# core_mcu.net
KiCad netlist of a schematic drawn in EAGLE
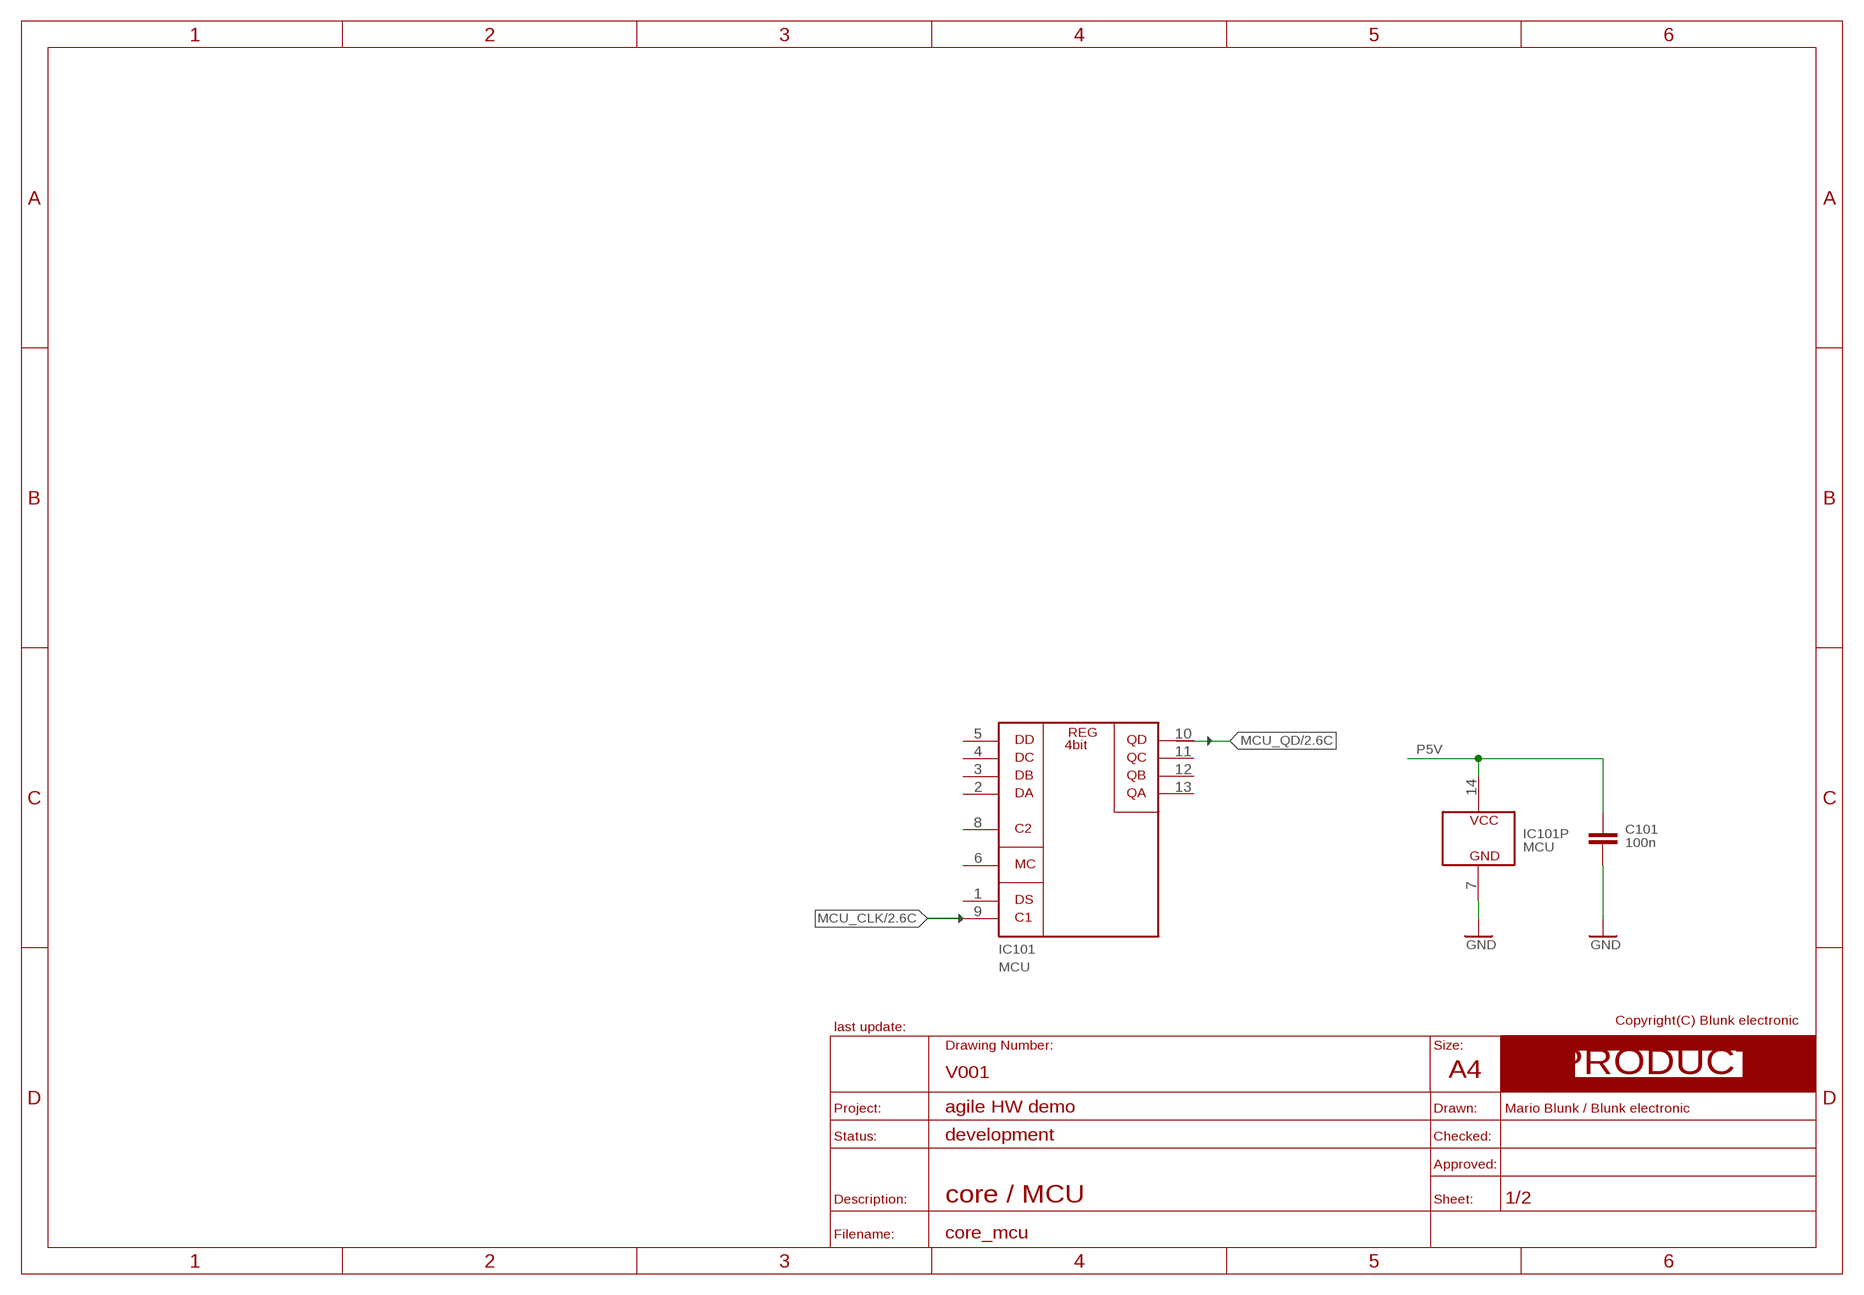
[diagram p0: schematic, sheet 1]
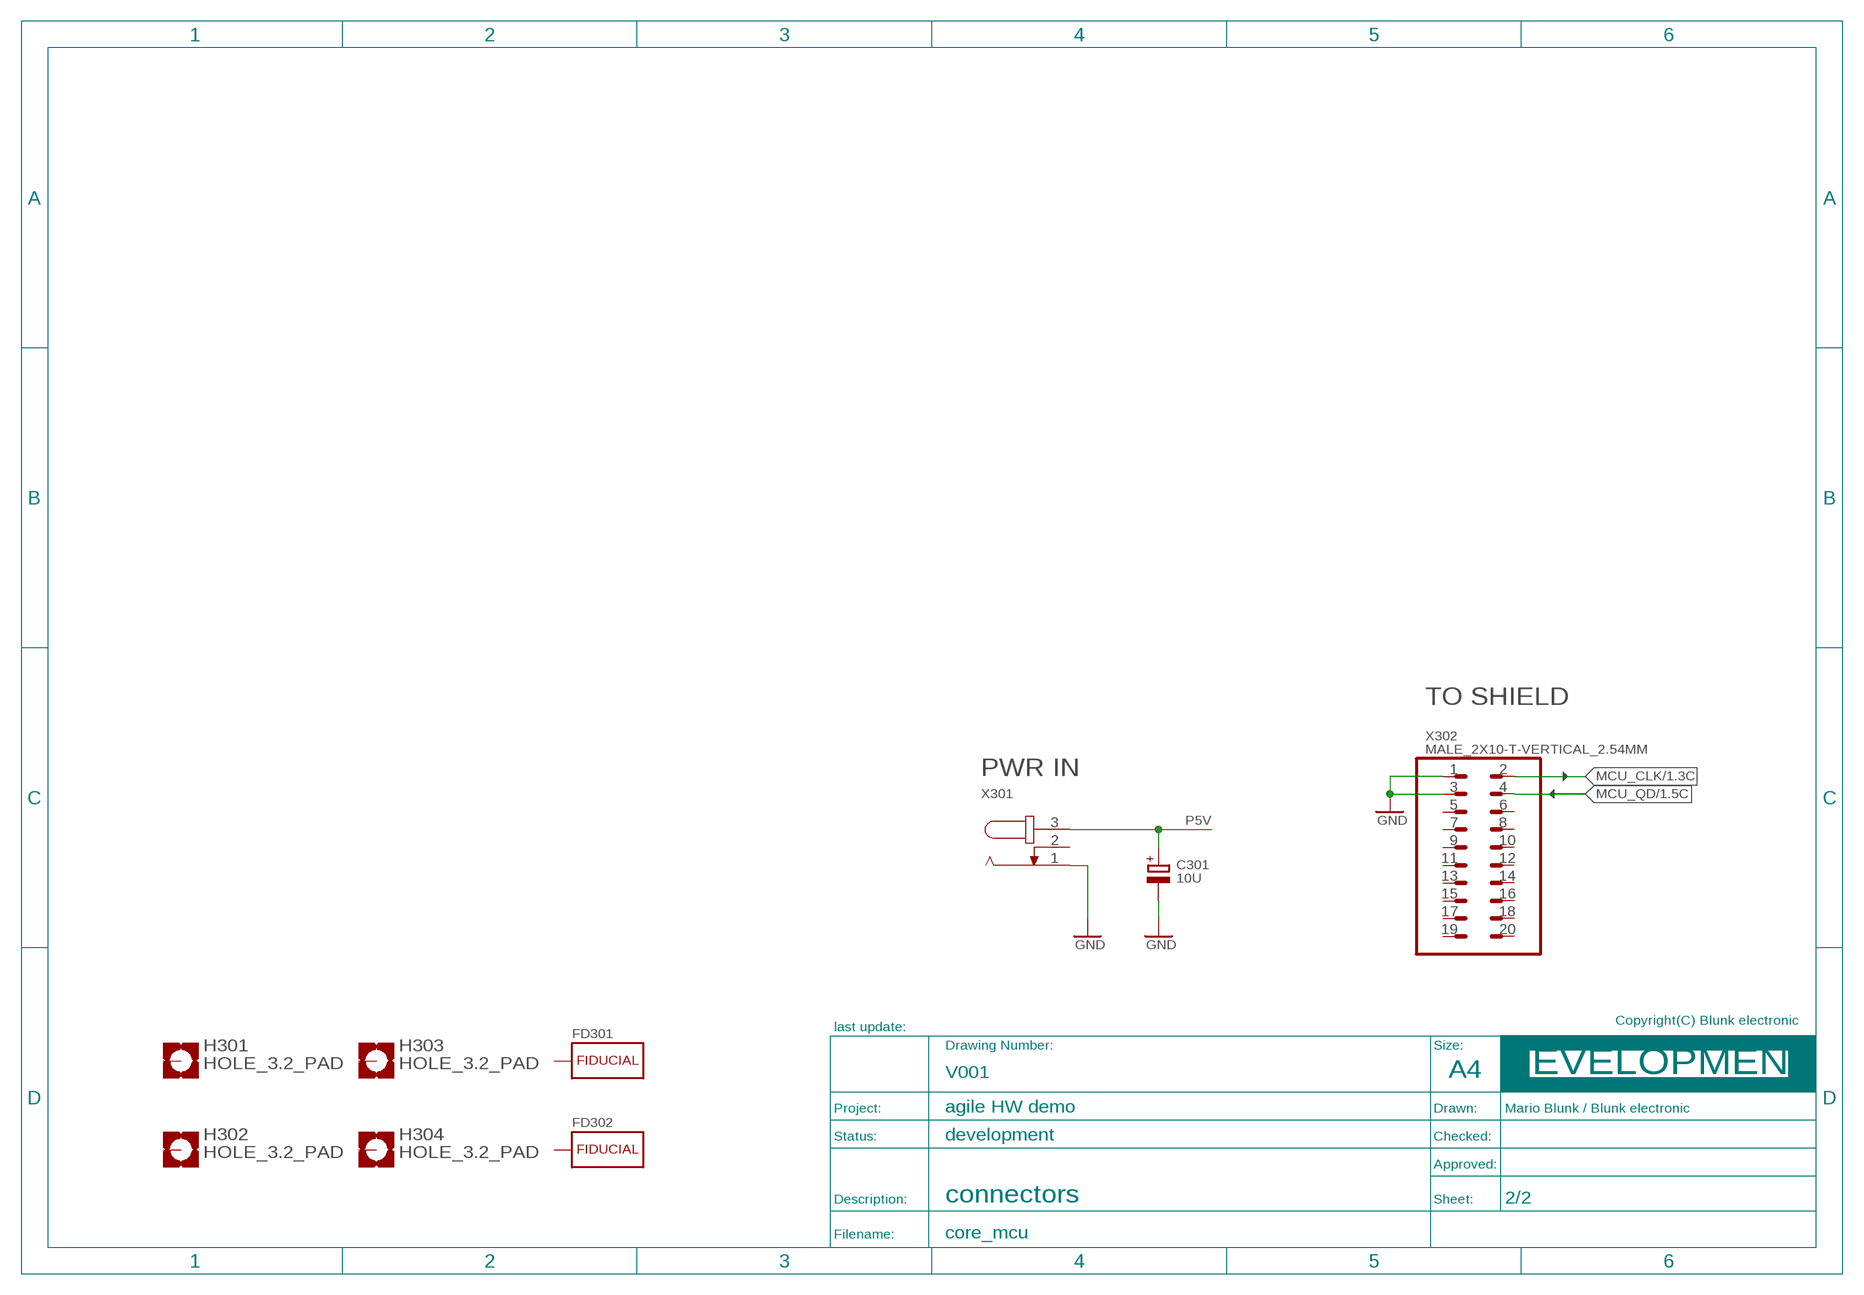
[diagram p1: schematic, sheet 2]

(export (version "E")
  (design (tool "Eeschema 10.0.6"))
  (components
    (comp (ref "C101")
      (value "100n")
      (footprint "eagle-import:S_0805")
      (libsource (lib "eagle-import") (part "C_S_0805"))
    )
    (comp (ref "IC101")
      (value "MCU")
      (footprint "eagle-import:T_NDIP14")
      (libsource (lib "eagle-import") (part "7495N"))
    )
    (comp (ref "C301")
      (value "10U")
      (footprint "eagle-import:S_6032")
      (libsource (lib "eagle-import") (part "C_POL_S_6032"))
    )
    (comp (ref "FD301")
      (value "FIDUCIAL_CROSSHAIR")
      (footprint "eagle-import:CROSSHAIR")
      (libsource (lib "eagle-import") (part "FIDUCIAL_CROSSHAIR"))
    )
    (comp (ref "FD302")
      (value "FIDUCIAL_CROSSHAIR")
      (footprint "eagle-import:CROSSHAIR")
      (libsource (lib "eagle-import") (part "FIDUCIAL_CROSSHAIR"))
    )
    (comp (ref "H301")
      (value "HOLE_3.2_PAD")
      (footprint "eagle-import:3.2_PAD")
      (libsource (lib "eagle-import") (part "HOLE_3.2_PAD"))
    )
    (comp (ref "H302")
      (value "HOLE_3.2_PAD")
      (footprint "eagle-import:3.2_PAD")
      (libsource (lib "eagle-import") (part "HOLE_3.2_PAD"))
    )
    (comp (ref "H303")
      (value "HOLE_3.2_PAD")
      (footprint "eagle-import:3.2_PAD")
      (libsource (lib "eagle-import") (part "HOLE_3.2_PAD"))
    )
    (comp (ref "H304")
      (value "HOLE_3.2_PAD")
      (footprint "eagle-import:3.2_PAD")
      (libsource (lib "eagle-import") (part "HOLE_3.2_PAD"))
    )
    (comp (ref "X301")
      (value "POWER_JACK-T-0")
      (footprint "eagle-import:T_POWER_JACK_SPC4077")
      (fields (field (name "FUNCTION") "PWR IN"))
      (libsource (lib "eagle-import") (part "POWER_JACK-T-0"))
    )
    (comp (ref "X302")
      (value "MALE_2X10-T-VERTICAL_2.54MM")
      (footprint "eagle-import:T_MALE_2X10_VERTICAL_GRID_2.54MM")
      (fields (field (name "FUNCTION") "TO SHIELD"))
      (libsource (lib "eagle-import") (part "MALE_2X10-T-VERTICAL_2.54MM"))
    )
  )
  (nets
    (net (code "1") (name "GND") (class "Default")
      (node (ref "C101") (pin "2") (pinfunction "2_2") (pintype "passive"))
      (node (ref "C301") (pin "-") (pinfunction "-_-") (pintype "passive"))
      (node (ref "IC101") (pin "7") (pinfunction "GND_7") (pintype "power_in"))
      (node (ref "X301") (pin "1") (pinfunction "1_1") (pintype "passive"))
      (node (ref "X302") (pin "1") (pinfunction "1_1") (pintype "passive"))
      (node (ref "X302") (pin "3") (pinfunction "3_3") (pintype "passive"))
    )
    (net (code "2") (name "MCU_CLK") (class "Default")
      (node (ref "IC101") (pin "9") (pinfunction "C1_9") (pintype "input"))
      (node (ref "X302") (pin "2") (pinfunction "2_2") (pintype "passive"))
    )
    (net (code "3") (name "MCU_QD") (class "Default")
      (node (ref "IC101") (pin "10") (pinfunction "QD_10") (pintype "output"))
      (node (ref "X302") (pin "4") (pinfunction "4_4") (pintype "passive"))
    )
    (net (code "4") (name "P5V") (class "Default")
      (node (ref "C101") (pin "1") (pinfunction "1_1") (pintype "passive"))
      (node (ref "C301") (pin "+") (pinfunction "+_+") (pintype "passive"))
      (node (ref "IC101") (pin "14") (pinfunction "VCC_14") (pintype "power_in"))
      (node (ref "X301") (pin "3") (pinfunction "3_3") (pintype "passive"))
    )
    (net (code "5") (name "unconnected-(FD301-NC-Pad1)") (class "Default")
      (node (ref "FD301") (pin "1") (pinfunction "NC_1") (pintype "no_connect"))
    )
    (net (code "6") (name "unconnected-(FD302-NC-Pad1)") (class "Default")
      (node (ref "FD302") (pin "1") (pinfunction "NC_1") (pintype "no_connect"))
    )
    (net (code "7") (name "unconnected-(H301-MOUNT-PadH1)") (class "Default")
      (node (ref "H301") (pin "H1") (pinfunction "MOUNT_H1") (pintype "passive"))
    )
    (net (code "8") (name "unconnected-(H302-MOUNT-PadH1)") (class "Default")
      (node (ref "H302") (pin "H1") (pinfunction "MOUNT_H1") (pintype "passive"))
    )
    (net (code "9") (name "unconnected-(H303-MOUNT-PadH1)") (class "Default")
      (node (ref "H303") (pin "H1") (pinfunction "MOUNT_H1") (pintype "passive"))
    )
    (net (code "10") (name "unconnected-(H304-MOUNT-PadH1)") (class "Default")
      (node (ref "H304") (pin "H1") (pinfunction "MOUNT_H1") (pintype "passive"))
    )
    (net (code "11") (name "unconnected-(IC101A-C2-Pad8)") (class "Default")
      (node (ref "IC101") (pin "8") (pinfunction "C2_8") (pintype "input"))
    )
    (net (code "12") (name "unconnected-(IC101A-DA-Pad2)") (class "Default")
      (node (ref "IC101") (pin "2") (pinfunction "DA_2") (pintype "input"))
    )
    (net (code "13") (name "unconnected-(IC101A-DB-Pad3)") (class "Default")
      (node (ref "IC101") (pin "3") (pinfunction "DB_3") (pintype "input"))
    )
    (net (code "14") (name "unconnected-(IC101A-DC-Pad4)") (class "Default")
      (node (ref "IC101") (pin "4") (pinfunction "DC_4") (pintype "input"))
    )
    (net (code "15") (name "unconnected-(IC101A-DD-Pad5)") (class "Default")
      (node (ref "IC101") (pin "5") (pinfunction "DD_5") (pintype "input"))
    )
    (net (code "16") (name "unconnected-(IC101A-DS-Pad1)") (class "Default")
      (node (ref "IC101") (pin "1") (pinfunction "DS_1") (pintype "input"))
    )
    (net (code "17") (name "unconnected-(IC101A-MC-Pad6)") (class "Default")
      (node (ref "IC101") (pin "6") (pinfunction "MC_6") (pintype "input"))
    )
    (net (code "18") (name "unconnected-(IC101A-QA-Pad13)") (class "Default")
      (node (ref "IC101") (pin "13") (pinfunction "QA_13") (pintype "output"))
    )
    (net (code "19") (name "unconnected-(IC101A-QB-Pad12)") (class "Default")
      (node (ref "IC101") (pin "12") (pinfunction "QB_12") (pintype "output"))
    )
    (net (code "20") (name "unconnected-(IC101A-QC-Pad11)") (class "Default")
      (node (ref "IC101") (pin "11") (pinfunction "QC_11") (pintype "output"))
    )
    (net (code "21") (name "unconnected-(X301-Pad2)") (class "Default")
      (node (ref "X301") (pin "2") (pinfunction "2_2") (pintype "passive"))
    )
    (net (code "22") (name "unconnected-(X302-Pad5)") (class "Default")
      (node (ref "X302") (pin "5") (pinfunction "5_5") (pintype "passive"))
    )
    (net (code "23") (name "unconnected-(X302-Pad6)") (class "Default")
      (node (ref "X302") (pin "6") (pinfunction "6_6") (pintype "passive"))
    )
    (net (code "24") (name "unconnected-(X302-Pad7)") (class "Default")
      (node (ref "X302") (pin "7") (pinfunction "7_7") (pintype "passive"))
    )
    (net (code "25") (name "unconnected-(X302-Pad8)") (class "Default")
      (node (ref "X302") (pin "8") (pinfunction "8_8") (pintype "passive"))
    )
    (net (code "26") (name "unconnected-(X302-Pad9)") (class "Default")
      (node (ref "X302") (pin "9") (pinfunction "9_9") (pintype "passive"))
    )
    (net (code "27") (name "unconnected-(X302-Pad10)") (class "Default")
      (node (ref "X302") (pin "10") (pinfunction "10_10") (pintype "passive"))
    )
    (net (code "28") (name "unconnected-(X302-Pad11)") (class "Default")
      (node (ref "X302") (pin "11") (pinfunction "11_11") (pintype "passive"))
    )
    (net (code "29") (name "unconnected-(X302-Pad12)") (class "Default")
      (node (ref "X302") (pin "12") (pinfunction "12_12") (pintype "passive"))
    )
    (net (code "30") (name "unconnected-(X302-Pad13)") (class "Default")
      (node (ref "X302") (pin "13") (pinfunction "13_13") (pintype "passive"))
    )
    (net (code "31") (name "unconnected-(X302-Pad14)") (class "Default")
      (node (ref "X302") (pin "14") (pinfunction "14_14") (pintype "passive"))
    )
    (net (code "32") (name "unconnected-(X302-Pad15)") (class "Default")
      (node (ref "X302") (pin "15") (pinfunction "15_15") (pintype "passive"))
    )
    (net (code "33") (name "unconnected-(X302-Pad16)") (class "Default")
      (node (ref "X302") (pin "16") (pinfunction "16_16") (pintype "passive"))
    )
    (net (code "34") (name "unconnected-(X302-Pad17)") (class "Default")
      (node (ref "X302") (pin "17") (pinfunction "17_17") (pintype "passive"))
    )
    (net (code "35") (name "unconnected-(X302-Pad18)") (class "Default")
      (node (ref "X302") (pin "18") (pinfunction "18_18") (pintype "passive"))
    )
    (net (code "36") (name "unconnected-(X302-Pad19)") (class "Default")
      (node (ref "X302") (pin "19") (pinfunction "19_19") (pintype "passive"))
    )
    (net (code "37") (name "unconnected-(X302-Pad20)") (class "Default")
      (node (ref "X302") (pin "20") (pinfunction "20_20") (pintype "passive"))
    )
  )
)
